# unity-gain-mixiple.net
KiCad netlist of a schematic drawn in EAGLE
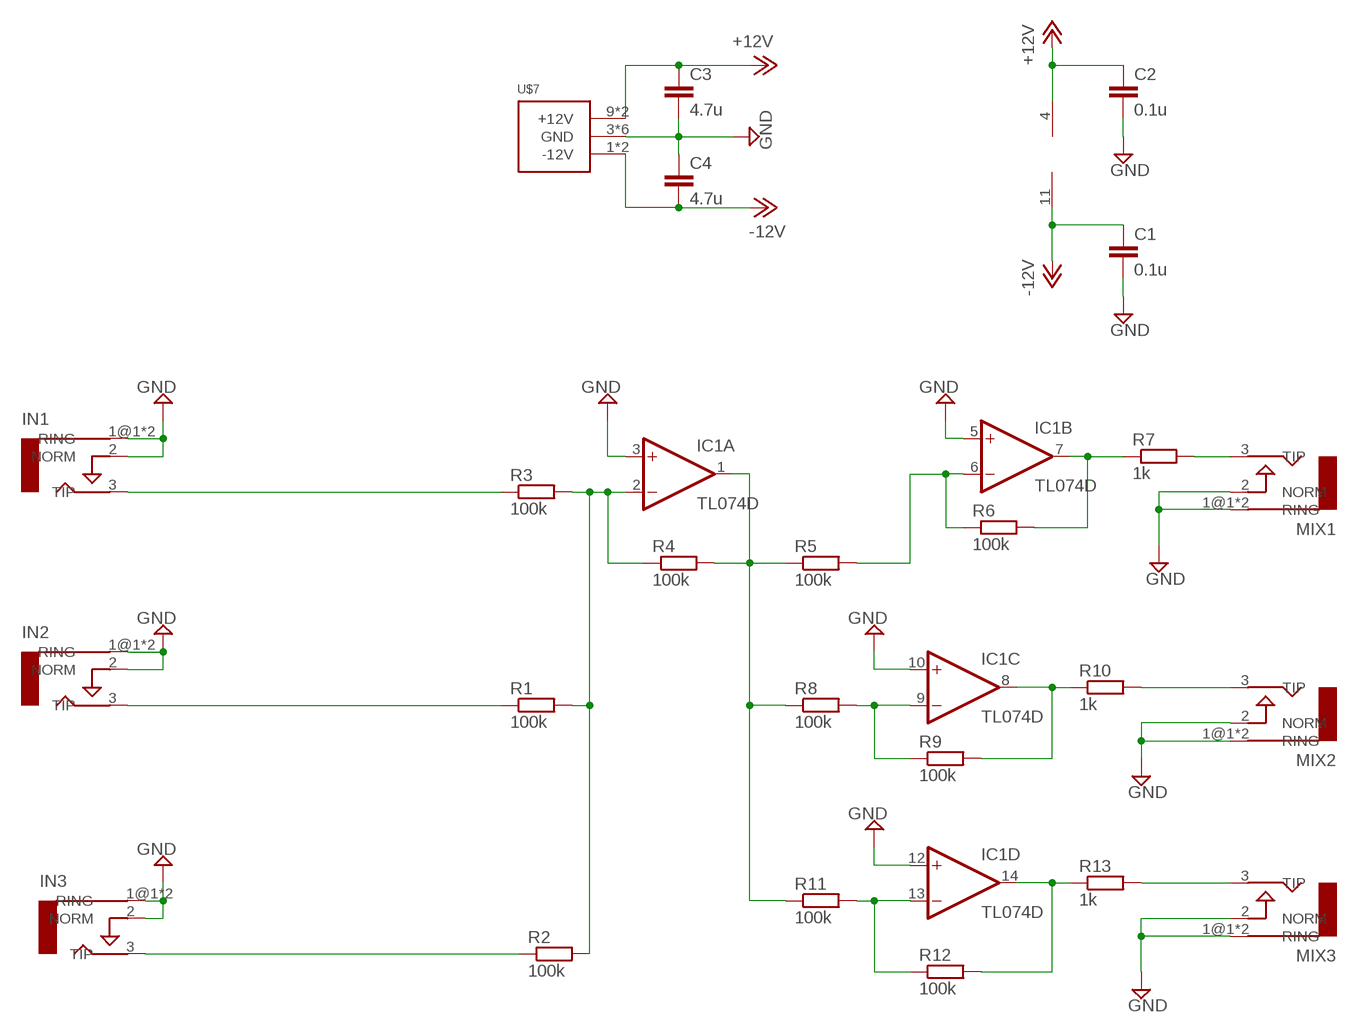
[diagram p0: schematic, sheet 1]

(export (version "E")
  (design (tool "Eeschema 10.0.6"))
  (components
    (comp (ref "C1")
      (value "0.1u")
      (footprint "eagle-import:C0805")
      (libsource (lib "eagle-import") (part "C-EUC0805"))
    )
    (comp (ref "C2")
      (value "0.1u")
      (footprint "eagle-import:C0805")
      (libsource (lib "eagle-import") (part "C-EUC0805"))
    )
    (comp (ref "C3")
      (value "4.7u")
      (footprint "eagle-import:C0805")
      (libsource (lib "eagle-import") (part "C-EUC0805"))
    )
    (comp (ref "C4")
      (value "4.7u")
      (footprint "eagle-import:C0805")
      (libsource (lib "eagle-import") (part "C-EUC0805"))
    )
    (comp (ref "IC1")
      (value "TL074D")
      (footprint "eagle-import:SO14")
      (libsource (lib "eagle-import") (part "TL074D"))
    )
    (comp (ref "IN1")
      (value "AUDIO-JACKERTHENVAR")
      (footprint "eagle-import:ERTHENVAR-JACK")
      (libsource (lib "eagle-import") (part "AUDIO-JACKERTHENVAR"))
    )
    (comp (ref "IN2")
      (value "AUDIO-JACKERTHENVAR")
      (footprint "eagle-import:ERTHENVAR-JACK")
      (libsource (lib "eagle-import") (part "AUDIO-JACKERTHENVAR"))
    )
    (comp (ref "IN3")
      (value "AUDIO-JACKERTHENVAR")
      (footprint "eagle-import:ERTHENVAR-JACK")
      (libsource (lib "eagle-import") (part "AUDIO-JACKERTHENVAR"))
    )
    (comp (ref "MIX1")
      (value "AUDIO-JACKERTHENVAR")
      (footprint "eagle-import:ERTHENVAR-JACK")
      (libsource (lib "eagle-import") (part "AUDIO-JACKERTHENVAR"))
    )
    (comp (ref "MIX2")
      (value "AUDIO-JACKERTHENVAR")
      (footprint "eagle-import:ERTHENVAR-JACK")
      (libsource (lib "eagle-import") (part "AUDIO-JACKERTHENVAR"))
    )
    (comp (ref "MIX3")
      (value "AUDIO-JACKERTHENVAR")
      (footprint "eagle-import:ERTHENVAR-JACK")
      (libsource (lib "eagle-import") (part "AUDIO-JACKERTHENVAR"))
    )
    (comp (ref "R1")
      (value "100k")
      (footprint "eagle-import:R0805")
      (libsource (lib "eagle-import") (part "R-EU_R0805"))
    )
    (comp (ref "R2")
      (value "100k")
      (footprint "eagle-import:R0805")
      (libsource (lib "eagle-import") (part "R-EU_R0805"))
    )
    (comp (ref "R3")
      (value "100k")
      (footprint "eagle-import:R0805")
      (libsource (lib "eagle-import") (part "R-EU_R0805"))
    )
    (comp (ref "R4")
      (value "100k")
      (footprint "eagle-import:R0805")
      (libsource (lib "eagle-import") (part "R-EU_R0805"))
    )
    (comp (ref "R5")
      (value "100k")
      (footprint "eagle-import:R0805")
      (libsource (lib "eagle-import") (part "R-EU_R0805"))
    )
    (comp (ref "R6")
      (value "100k")
      (footprint "eagle-import:R0805")
      (libsource (lib "eagle-import") (part "R-EU_R0805"))
    )
    (comp (ref "R7")
      (value "1k")
      (footprint "eagle-import:R0805")
      (libsource (lib "eagle-import") (part "R-EU_R0805"))
    )
    (comp (ref "R8")
      (value "100k")
      (footprint "eagle-import:R0805")
      (libsource (lib "eagle-import") (part "R-EU_R0805"))
    )
    (comp (ref "R9")
      (value "100k")
      (footprint "eagle-import:R0805")
      (libsource (lib "eagle-import") (part "R-EU_R0805"))
    )
    (comp (ref "R10")
      (value "1k")
      (footprint "eagle-import:R0805")
      (libsource (lib "eagle-import") (part "R-EU_R0805"))
    )
    (comp (ref "R11")
      (value "100k")
      (footprint "eagle-import:R0805")
      (libsource (lib "eagle-import") (part "R-EU_R0805"))
    )
    (comp (ref "R12")
      (value "100k")
      (footprint "eagle-import:R0805")
      (libsource (lib "eagle-import") (part "R-EU_R0805"))
    )
    (comp (ref "R13")
      (value "1k")
      (footprint "eagle-import:R0805")
      (libsource (lib "eagle-import") (part "R-EU_R0805"))
    )
    (comp (ref "U$7")
      (value "POWER_SIMPLE10")
      (footprint "eagle-import:POWER_10")
      (libsource (lib "eagle-import") (part "POWER_SIMPLE10"))
    )
  )
  (nets
    (net (code "1") (name "+12V") (class "Default")
      (node (ref "C2") (pin "1") (pinfunction "1_1") (pintype "passive"))
      (node (ref "C3") (pin "1") (pinfunction "1_1") (pintype "passive"))
      (node (ref "IC1") (pin "4") (pinfunction "V+_4") (pintype "power_in"))
      (node (ref "U$7") (pin "10") (pinfunction "+12V_10") (pintype "bidirectional"))
      (node (ref "U$7") (pin "9") (pinfunction "+12V_9") (pintype "bidirectional"))
    )
    (net (code "2") (name "-12V") (class "Default")
      (node (ref "C1") (pin "1") (pinfunction "1_1") (pintype "passive"))
      (node (ref "C4") (pin "2") (pinfunction "2_2") (pintype "passive"))
      (node (ref "IC1") (pin "11") (pinfunction "V-_11") (pintype "power_in"))
      (node (ref "U$7") (pin "1") (pinfunction "-12V_1") (pintype "bidirectional"))
      (node (ref "U$7") (pin "2") (pinfunction "-12V_2") (pintype "bidirectional"))
    )
    (net (code "3") (name "GND") (class "Default")
      (node (ref "C1") (pin "2") (pinfunction "2_2") (pintype "passive"))
      (node (ref "C2") (pin "2") (pinfunction "2_2") (pintype "passive"))
      (node (ref "C3") (pin "2") (pinfunction "2_2") (pintype "passive"))
      (node (ref "C4") (pin "1") (pinfunction "1_1") (pintype "passive"))
      (node (ref "IC1") (pin "10") (pinfunction "+IN_10") (pintype "input"))
      (node (ref "IC1") (pin "12") (pinfunction "+IN_12") (pintype "input"))
      (node (ref "IC1") (pin "3") (pinfunction "+IN_3") (pintype "input"))
      (node (ref "IC1") (pin "5") (pinfunction "+IN_5") (pintype "input"))
      (node (ref "IN1") (pin "1@1") (pinfunction "RING_1@1") (pintype "bidirectional"))
      (node (ref "IN1") (pin "1@2") (pinfunction "RING_1@2") (pintype "bidirectional"))
      (node (ref "IN1") (pin "2") (pinfunction "NORM_2") (pintype "bidirectional"))
      (node (ref "IN2") (pin "1@1") (pinfunction "RING_1@1") (pintype "bidirectional"))
      (node (ref "IN2") (pin "1@2") (pinfunction "RING_1@2") (pintype "bidirectional"))
      (node (ref "IN2") (pin "2") (pinfunction "NORM_2") (pintype "bidirectional"))
      (node (ref "IN3") (pin "1@1") (pinfunction "RING_1@1") (pintype "bidirectional"))
      (node (ref "IN3") (pin "1@2") (pinfunction "RING_1@2") (pintype "bidirectional"))
      (node (ref "IN3") (pin "2") (pinfunction "NORM_2") (pintype "bidirectional"))
      (node (ref "MIX1") (pin "1@1") (pinfunction "RING_1@1") (pintype "bidirectional"))
      (node (ref "MIX1") (pin "1@2") (pinfunction "RING_1@2") (pintype "bidirectional"))
      (node (ref "MIX1") (pin "2") (pinfunction "NORM_2") (pintype "bidirectional"))
      (node (ref "MIX2") (pin "1@1") (pinfunction "RING_1@1") (pintype "bidirectional"))
      (node (ref "MIX2") (pin "1@2") (pinfunction "RING_1@2") (pintype "bidirectional"))
      (node (ref "MIX2") (pin "2") (pinfunction "NORM_2") (pintype "bidirectional"))
      (node (ref "MIX3") (pin "1@1") (pinfunction "RING_1@1") (pintype "bidirectional"))
      (node (ref "MIX3") (pin "1@2") (pinfunction "RING_1@2") (pintype "bidirectional"))
      (node (ref "MIX3") (pin "2") (pinfunction "NORM_2") (pintype "bidirectional"))
      (node (ref "U$7") (pin "3") (pinfunction "GND_3") (pintype "bidirectional"))
      (node (ref "U$7") (pin "4") (pinfunction "GND_4") (pintype "bidirectional"))
      (node (ref "U$7") (pin "5") (pinfunction "GND_5") (pintype "bidirectional"))
      (node (ref "U$7") (pin "6") (pinfunction "GND_6") (pintype "bidirectional"))
      (node (ref "U$7") (pin "7") (pinfunction "GND_7") (pintype "bidirectional"))
      (node (ref "U$7") (pin "8") (pinfunction "GND_8") (pintype "bidirectional"))
    )
    (net (code "4") (name "Net-(IC1A--IN)") (class "Default")
      (node (ref "IC1") (pin "2") (pinfunction "-IN_2") (pintype "input"))
      (node (ref "R1") (pin "2") (pinfunction "2_2") (pintype "passive"))
      (node (ref "R2") (pin "2") (pinfunction "2_2") (pintype "passive"))
      (node (ref "R3") (pin "2") (pinfunction "2_2") (pintype "passive"))
      (node (ref "R4") (pin "1") (pinfunction "1_1") (pintype "passive"))
    )
    (net (code "5") (name "Net-(IC1A-OUT)") (class "Default")
      (node (ref "IC1") (pin "1") (pinfunction "OUT_1") (pintype "output"))
      (node (ref "R11") (pin "1") (pinfunction "1_1") (pintype "passive"))
      (node (ref "R4") (pin "2") (pinfunction "2_2") (pintype "passive"))
      (node (ref "R5") (pin "1") (pinfunction "1_1") (pintype "passive"))
      (node (ref "R8") (pin "1") (pinfunction "1_1") (pintype "passive"))
    )
    (net (code "6") (name "Net-(IC1B--IN)") (class "Default")
      (node (ref "IC1") (pin "6") (pinfunction "-IN_6") (pintype "input"))
      (node (ref "R5") (pin "2") (pinfunction "2_2") (pintype "passive"))
      (node (ref "R6") (pin "1") (pinfunction "1_1") (pintype "passive"))
    )
    (net (code "7") (name "Net-(IC1B-OUT)") (class "Default")
      (node (ref "IC1") (pin "7") (pinfunction "OUT_7") (pintype "output"))
      (node (ref "R6") (pin "2") (pinfunction "2_2") (pintype "passive"))
      (node (ref "R7") (pin "1") (pinfunction "1_1") (pintype "passive"))
    )
    (net (code "8") (name "Net-(IC1C--IN)") (class "Default")
      (node (ref "IC1") (pin "9") (pinfunction "-IN_9") (pintype "input"))
      (node (ref "R8") (pin "2") (pinfunction "2_2") (pintype "passive"))
      (node (ref "R9") (pin "1") (pinfunction "1_1") (pintype "passive"))
    )
    (net (code "9") (name "Net-(IC1C-OUT)") (class "Default")
      (node (ref "IC1") (pin "8") (pinfunction "OUT_8") (pintype "output"))
      (node (ref "R10") (pin "1") (pinfunction "1_1") (pintype "passive"))
      (node (ref "R9") (pin "2") (pinfunction "2_2") (pintype "passive"))
    )
    (net (code "10") (name "Net-(IC1D--IN)") (class "Default")
      (node (ref "IC1") (pin "13") (pinfunction "-IN_13") (pintype "input"))
      (node (ref "R11") (pin "2") (pinfunction "2_2") (pintype "passive"))
      (node (ref "R12") (pin "1") (pinfunction "1_1") (pintype "passive"))
    )
    (net (code "11") (name "Net-(IC1D-OUT)") (class "Default")
      (node (ref "IC1") (pin "14") (pinfunction "OUT_14") (pintype "output"))
      (node (ref "R12") (pin "2") (pinfunction "2_2") (pintype "passive"))
      (node (ref "R13") (pin "1") (pinfunction "1_1") (pintype "passive"))
    )
    (net (code "12") (name "Net-(IN1-TIP)") (class "Default")
      (node (ref "IN1") (pin "3") (pinfunction "TIP_3") (pintype "bidirectional"))
      (node (ref "R3") (pin "1") (pinfunction "1_1") (pintype "passive"))
    )
    (net (code "13") (name "Net-(IN2-TIP)") (class "Default")
      (node (ref "IN2") (pin "3") (pinfunction "TIP_3") (pintype "bidirectional"))
      (node (ref "R1") (pin "1") (pinfunction "1_1") (pintype "passive"))
    )
    (net (code "14") (name "Net-(IN3-TIP)") (class "Default")
      (node (ref "IN3") (pin "3") (pinfunction "TIP_3") (pintype "bidirectional"))
      (node (ref "R2") (pin "1") (pinfunction "1_1") (pintype "passive"))
    )
    (net (code "15") (name "Net-(MIX1-TIP)") (class "Default")
      (node (ref "MIX1") (pin "3") (pinfunction "TIP_3") (pintype "bidirectional"))
      (node (ref "R7") (pin "2") (pinfunction "2_2") (pintype "passive"))
    )
    (net (code "16") (name "Net-(MIX2-TIP)") (class "Default")
      (node (ref "MIX2") (pin "3") (pinfunction "TIP_3") (pintype "bidirectional"))
      (node (ref "R10") (pin "2") (pinfunction "2_2") (pintype "passive"))
    )
    (net (code "17") (name "Net-(MIX3-TIP)") (class "Default")
      (node (ref "MIX3") (pin "3") (pinfunction "TIP_3") (pintype "bidirectional"))
      (node (ref "R13") (pin "2") (pinfunction "2_2") (pintype "passive"))
    )
  )
)
